# Main_sch.net
KiCad netlist of a schematic drawn in Altium Designer
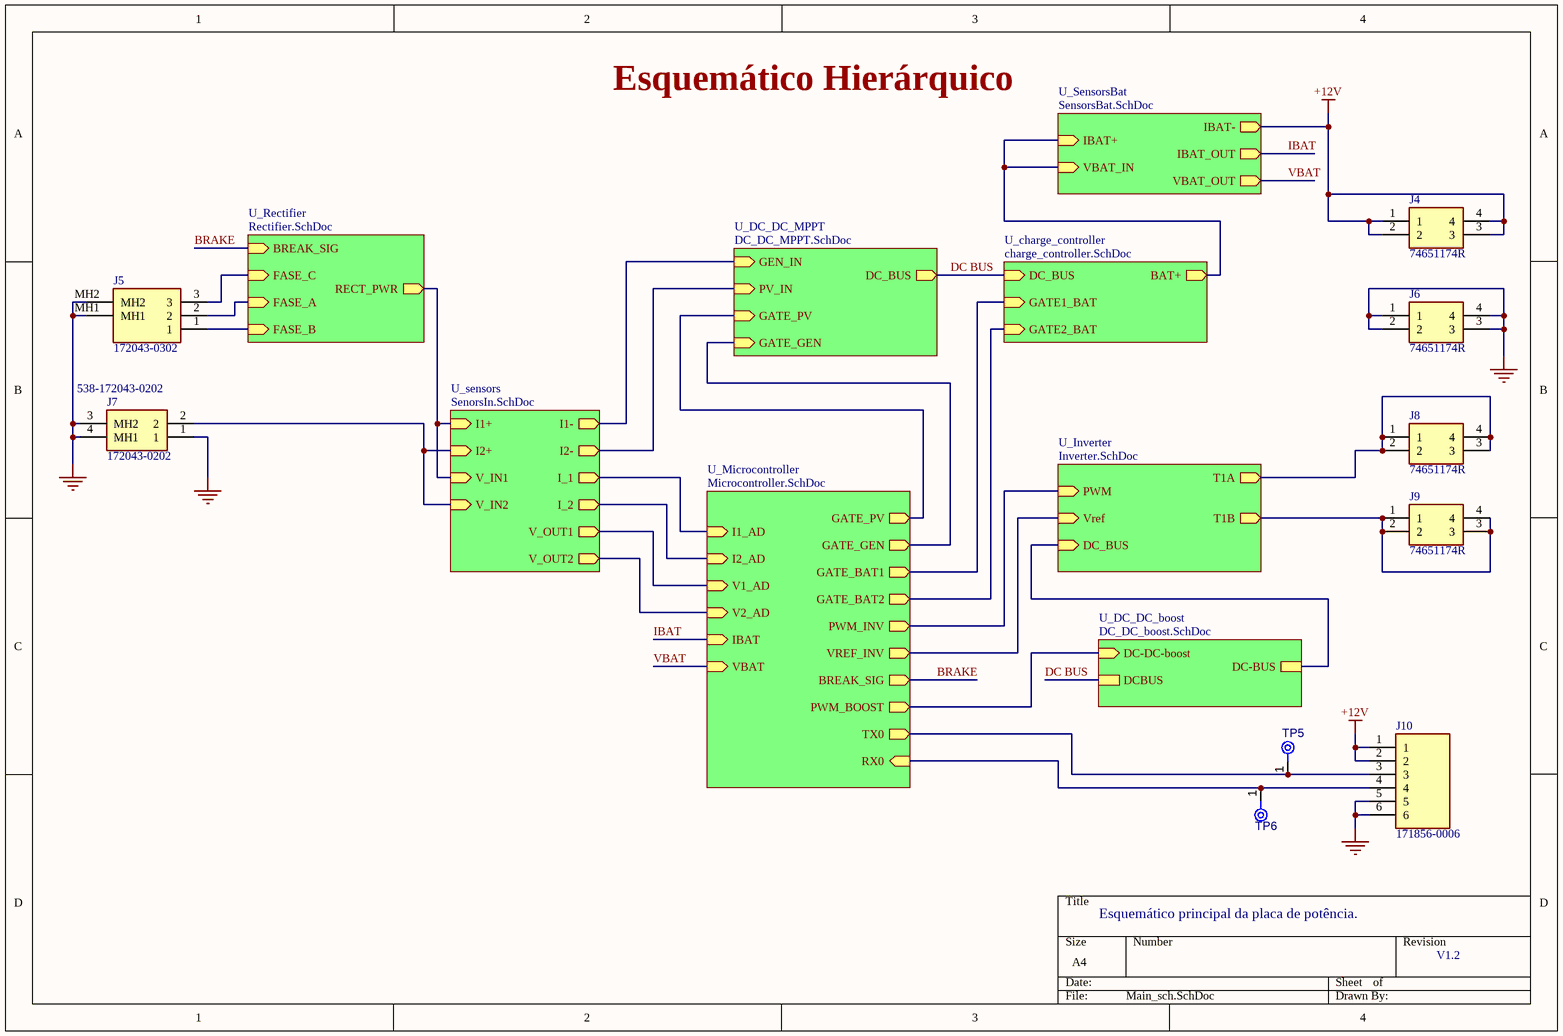
[diagram p0: Main_sch.SchDoc]

(export (version "E")
  (design (tool "Eeschema 10.0.6"))
  (components
    (comp (ref "J4")
      (value "74651174R")
      (footprint "PcbLib1:74651174R")
      (description "SHANK, THR")
      (fields
        (field (name "MOUSER PART NUMBER") "710-74651174R")
        (field (name "MANUFACTURER") "Wurth Electronics")
      )
      (libsource (lib "*") (part "74651174R"))
    )
    (comp (ref "J5")
      (value "172043-0302")
      (footprint "PcbLib1:1720430302")
      (description "Conn Power HDR 3 POS 7.49mm Solder RA Thru-Hole 3 Terminal 1 Port Super Sabre™ Frame")
      (fields (field (name "MANUFACTURER") "Molex") (field (name "MANUFACTURER PART NUMBER") "1720430302"))
      (libsource (lib "pi2") (part "172043-0302"))
    )
    (comp (ref "J6")
      (value "74651174R")
      (footprint "PcbLib1:74651174R")
      (description "SHANK, THR")
      (fields
        (field (name "MOUSER PART NUMBER") "710-74651174R")
        (field (name "MANUFACTURER") "Wurth Electronics")
      )
      (libsource (lib "*") (part "74651174R"))
    )
    (comp (ref "J7")
      (value "172043-0202")
      (footprint "PcbLib1:1720430202")
      (description "CONN HDR 2POS 7.50MM R/A SLDR")
      (fields
        (field (name "MOUSER PART NUMBER") "538-172043-0202")
        (field (name "SUPPLIER PART NUMBER 1") "538-172043-0202")
        (field (name "MANUFACTURER") "Molex")
      )
      (libsource (lib "pi2") (part "172043-0202"))
    )
    (comp (ref "J8")
      (value "74651174R")
      (footprint "PcbLib1:74651174R")
      (description "SHANK, THR")
      (fields
        (field (name "MOUSER PART NUMBER") "710-74651174R")
        (field (name "MANUFACTURER") "Wurth Electronics")
      )
      (libsource (lib "*") (part "74651174R"))
    )
    (comp (ref "J9")
      (value "74651174R")
      (footprint "PcbLib1:74651174R")
      (description "SHANK, THR")
      (fields
        (field (name "MOUSER PART NUMBER") "710-74651174R")
        (field (name "MANUFACTURER") "Wurth Electronics")
      )
      (libsource (lib "*") (part "74651174R"))
    )
    (comp (ref "J10")
      (value "171856-0006")
      (footprint "PcbLib1:HDRV6W99P0X254_1X6_1509X635X1100P")
      (description "Conn Wire to Board HDR 6 POS 2.54mm Solder ST Thru-Hole KK® Bag")
      (fields (field (name "MOUSER PART NUMBER") "538-171856-0006") (field (name "MANUFACTURER") "Molex"))
      (libsource (lib "*") (part "171856-0006"))
    )
    (comp (ref "TP5")
      (value "TPAD6R")
      (footprint "TP06R")
      (description "0.6mm round")
      (libsource (lib "PI2") (part "CMP-001-0001-4"))
    )
    (comp (ref "TP6")
      (value "TPAD6R")
      (footprint "TP06R")
      (description "0.6mm round")
      (libsource (lib "PI2") (part "CMP-001-0001-4"))
    )
  )
  (nets
    (net (code "1") (name "+12V") (class "Default")
      (node (ref "J10") (pin "1") (pinfunction "1_1") (pintype "passive"))
      (node (ref "J10") (pin "2") (pinfunction "2_2") (pintype "passive"))
      (node (ref "J4") (pin "1") (pinfunction "1_1") (pintype "passive"))
      (node (ref "J4") (pin "2") (pinfunction "2_2") (pintype "passive"))
      (node (ref "J4") (pin "3") (pinfunction "3_3") (pintype "passive"))
      (node (ref "J4") (pin "4") (pinfunction "4_4") (pintype "passive"))
    )
    (net (code "6") (name "/FASE_A") (class "Default")
      (node (ref "J5") (pin "2") (pinfunction "2_2") (pintype "passive"))
    )
    (net (code "7") (name "/FASE_B") (class "Default")
      (node (ref "J5") (pin "1") (pinfunction "1_1") (pintype "passive"))
    )
    (net (code "8") (name "/FASE_C") (class "Default")
      (node (ref "J5") (pin "3") (pinfunction "3_3") (pintype "passive"))
    )
    (net (code "14") (name "/I2+") (class "Default")
      (node (ref "J7") (pin "2") (pinfunction "2_2") (pintype "passive"))
    )
    (net (code "22") (name "/RX0") (class "Default")
      (node (ref "J10") (pin "4") (pinfunction "4_4") (pintype "passive"))
      (node (ref "TP6") (pin "1") (pinfunction "TP_1") (pintype "passive"))
    )
    (net (code "23") (name "/T1A") (class "Default")
      (node (ref "J8") (pin "1") (pinfunction "1_1") (pintype "passive"))
      (node (ref "J8") (pin "2") (pinfunction "2_2") (pintype "passive"))
      (node (ref "J8") (pin "3") (pinfunction "3_3") (pintype "passive"))
      (node (ref "J8") (pin "4") (pinfunction "4_4") (pintype "passive"))
    )
    (net (code "24") (name "/T1B") (class "Default")
      (node (ref "J9") (pin "1") (pinfunction "1_1") (pintype "passive"))
      (node (ref "J9") (pin "2") (pinfunction "2_2") (pintype "passive"))
      (node (ref "J9") (pin "3") (pinfunction "3_3") (pintype "passive"))
      (node (ref "J9") (pin "4") (pinfunction "4_4") (pintype "passive"))
    )
    (net (code "25") (name "/TX0") (class "Default")
      (node (ref "J10") (pin "3") (pinfunction "3_3") (pintype "passive"))
      (node (ref "TP5") (pin "1") (pinfunction "TP_1") (pintype "passive"))
    )
    (net (code "30") (name "GND") (class "Default")
      (node (ref "J10") (pin "5") (pinfunction "5_5") (pintype "passive"))
      (node (ref "J10") (pin "6") (pinfunction "6_6") (pintype "passive"))
      (node (ref "J5") (pin "MH1") (pinfunction "MH1_MH1") (pintype "passive"))
      (node (ref "J5") (pin "MH2") (pinfunction "MH2_MH2") (pintype "passive"))
      (node (ref "J6") (pin "1") (pinfunction "1_1") (pintype "passive"))
      (node (ref "J6") (pin "2") (pinfunction "2_2") (pintype "passive"))
      (node (ref "J6") (pin "3") (pinfunction "3_3") (pintype "passive"))
      (node (ref "J6") (pin "4") (pinfunction "4_4") (pintype "passive"))
      (node (ref "J7") (pin "1") (pinfunction "1_1") (pintype "passive"))
      (node (ref "J7") (pin "3") (pinfunction "MH2_3") (pintype "passive"))
      (node (ref "J7") (pin "4") (pinfunction "MH1_4") (pintype "passive"))
    )
  )
)
